# Ground_splitter.net
KiCad netlist of a schematic drawn in EAGLE
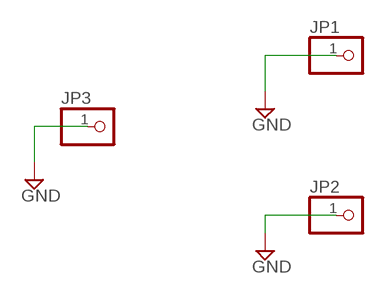
[diagram p0: schematic, sheet 1]

(export (version "E")
  (design (tool "Eeschema 10.0.6"))
  (components
    (comp (ref "JP1")
      (value "PINHD-1X1")
      (footprint "eagle-import:1X01")
      (libsource (lib "eagle-import") (part "PINHD-1X1"))
    )
    (comp (ref "JP2")
      (value "PINHD-1X1")
      (footprint "eagle-import:1X01")
      (libsource (lib "eagle-import") (part "PINHD-1X1"))
    )
    (comp (ref "JP3")
      (value "PINHD-1X1")
      (footprint "eagle-import:1X01")
      (libsource (lib "eagle-import") (part "PINHD-1X1"))
    )
  )
  (nets
    (net (code "1") (name "GND") (class "Default")
      (node (ref "JP1") (pin "1") (pinfunction "1_1") (pintype "passive"))
      (node (ref "JP2") (pin "1") (pinfunction "1_1") (pintype "passive"))
      (node (ref "JP3") (pin "1") (pinfunction "1_1") (pintype "passive"))
    )
  )
)
